# 1_power.net
KiCad netlist of a schematic drawn in Altium Designer
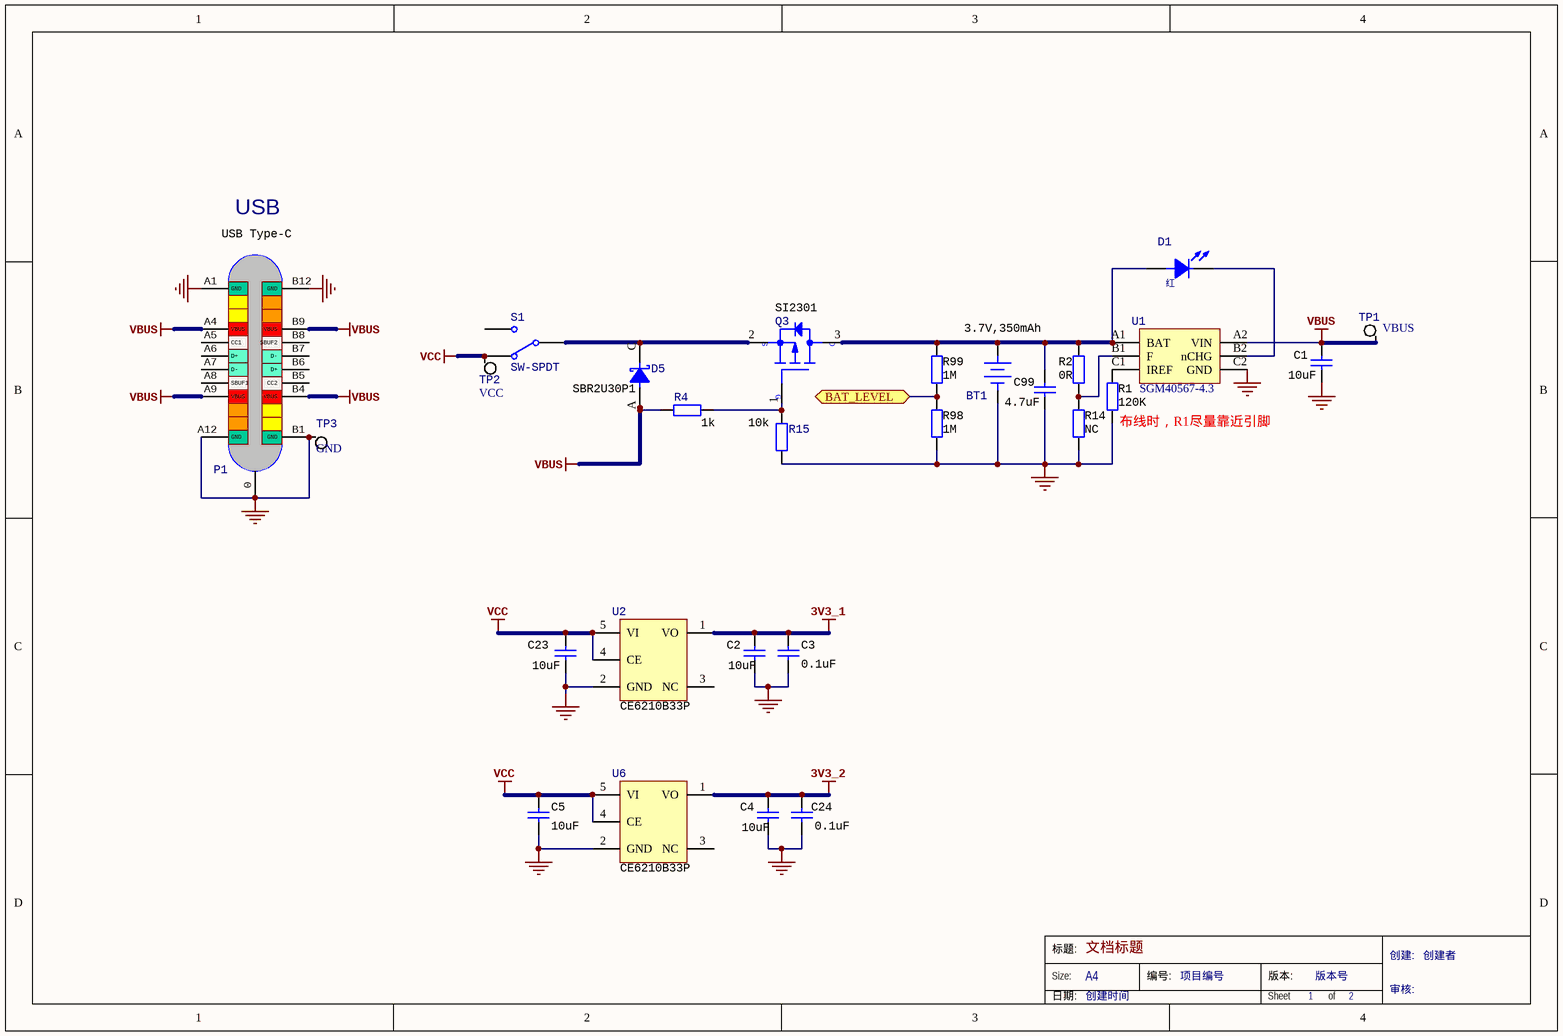
[diagram p0: 1.power.SchDoc]

(export (version "E")
  (design (tool "Eeschema 10.0.6"))
  (components
    (comp (ref "BT1")
      (value "3.7V,350mAh")
      (footprint "2P/1.0MM立式贴片座子")
      (description "4.2V Li-lon")
      (fields (field (name "MANUFACTURER") "?"))
      (libsource (lib "03.常用器件") (part "Battery"))
    )
    (comp (ref "C1")
      (value "10uF")
      (footprint "0603")
      (description "CAP, CERM, 0.01uF, 100V, +/-5%, X7R, 0603")
      (fields (field (name "PARTNUMBER") "06031C103JAT2A") (field (name "MANUFACTURER") "AVX"))
      (libsource (lib "03.常用器件") (part "CAP1_npol"))
    )
    (comp (ref "C2")
      (value "10uF")
      (footprint "0603")
      (description "CAP, CERM, 0.01uF, 100V, +/-5%, X7R, 0603")
      (fields (field (name "PARTNUMBER") "06031C103JAT2A") (field (name "MANUFACTURER") "AVX"))
      (libsource (lib "03.常用器件") (part "CAP1_npol"))
    )
    (comp (ref "C3")
      (value "0.1uF")
      (footprint "0402")
      (description "CAP, CERM, 0.01uF, 100V, +/-5%, X7R, 0603")
      (fields (field (name "PARTNUMBER") "06031C103JAT2A") (field (name "MANUFACTURER") "AVX"))
      (libsource (lib "03.常用器件") (part "CAP1_npol"))
    )
    (comp (ref "C4")
      (value "10uF")
      (footprint "0603")
      (description "CAP, CERM, 0.01uF, 100V, +/-5%, X7R, 0603")
      (fields (field (name "PARTNUMBER") "06031C103JAT2A") (field (name "MANUFACTURER") "AVX"))
      (libsource (lib "03.常用器件") (part "CAP1_npol"))
    )
    (comp (ref "C5")
      (value "10uF")
      (footprint "0603")
      (description "CAP, CERM, 0.01uF, 100V, +/-5%, X7R, 0603")
      (fields (field (name "PARTNUMBER") "06031C103JAT2A") (field (name "MANUFACTURER") "AVX"))
      (libsource (lib "03.常用器件") (part "CAP1_npol"))
    )
    (comp (ref "C23")
      (value "10uF")
      (footprint "0603")
      (description "CAP, CERM, 0.01uF, 100V, +/-5%, X7R, 0603")
      (fields (field (name "PARTNUMBER") "06031C103JAT2A") (field (name "MANUFACTURER") "AVX"))
      (libsource (lib "03.常用器件") (part "CAP1_npol"))
    )
    (comp (ref "C24")
      (value "0.1uF")
      (footprint "0402")
      (description "CAP, CERM, 0.01uF, 100V, +/-5%, X7R, 0603")
      (fields (field (name "PARTNUMBER") "06031C103JAT2A") (field (name "MANUFACTURER") "AVX"))
      (libsource (lib "03.常用器件") (part "CAP1_npol"))
    )
    (comp (ref "C99")
      (value "4.7uF")
      (footprint "0603")
      (description "CAP, CERM, 0.01uF, 100V, +/-5%, X7R, 0603")
      (fields (field (name "PARTNUMBER") "06031C103JAT2A") (field (name "MANUFACTURER") "AVX"))
      (libsource (lib "03.常用器件") (part "CAP1_npol"))
    )
    (comp (ref "D1")
      (value "红")
      (footprint "0603LED")
      (fields (field (name "MANUFACTURER") "?"))
      (libsource (lib "03.常用器件") (part "LED1"))
    )
    (comp (ref "D5")
      (value "SBR2U30P1")
      (footprint "POWERDI123")
      (fields (field (name "PARTNUMBER") "?") (field (name "PUBLISHER") "Altium Limited"))
      (libsource (lib "03.常用器件") (part "Diode_Schottky"))
    )
    (comp (ref "P1")
      (value "USB Type-C")
      (footprint "TYPC-16PIN")
      (libsource (lib "USB Type-C") (part "USB Type-C"))
    )
    (comp (ref "Q3")
      (value "SI2301")
      (footprint "SOT23-3")
      (fields (field (name "MANUFACTURER") "?"))
      (libsource (lib "03.常用器件") (part "PMOS"))
    )
    (comp (ref "R1")
      (value "120K")
      (footprint "0402")
      (description "RES, 1.0k ohm, 5%, 0.1W, 0603")
      (fields
        (field (name "PARTNUMBER") "RC0603JR-071KL")
        (field (name "MANUFACTURER") "Yageo America")
        (field (name "PUBLISHER") "Texas Instruments")
      )
      (libsource (lib "03.常用器件") (part "RES1"))
    )
    (comp (ref "R2")
      (value "0R")
      (footprint "0402")
      (description "RES, 1.0k ohm, 5%, 0.1W, 0603")
      (fields
        (field (name "PARTNUMBER") "RC0603JR-071KL")
        (field (name "MANUFACTURER") "Yageo America")
        (field (name "PUBLISHER") "Texas Instruments")
      )
      (libsource (lib "") (part "RES1_1"))
    )
    (comp (ref "R4")
      (value "1k")
      (footprint "R0402")
      (description "Resistor")
      (fields (field (name "PUBLISHER") "Altium Limited"))
      (libsource (lib "Miscellaneous Devices") (part "Res2"))
    )
    (comp (ref "R14")
      (value "NC")
      (footprint "0402")
      (description "RES, 1.0k ohm, 5%, 0.1W, 0603")
      (fields
        (field (name "PARTNUMBER") "RC0603JR-071KL")
        (field (name "MANUFACTURER") "Yageo America")
        (field (name "PUBLISHER") "Texas Instruments")
      )
      (libsource (lib "") (part "RES1_1"))
    )
    (comp (ref "R15")
      (value "10k")
      (footprint "R0402")
      (description "Resistor")
      (fields (field (name "PUBLISHER") "Altium Limited"))
      (libsource (lib "") (part "Res2_1"))
    )
    (comp (ref "R98")
      (value "1M")
      (footprint "0402")
      (description "RES, 1.0k ohm, 5%, 0.1W, 0603")
      (fields
        (field (name "PARTNUMBER") "RC0603JR-071KL")
        (field (name "MANUFACTURER") "Yageo America")
        (field (name "PUBLISHER") "Texas Instruments")
      )
      (libsource (lib "03.常用器件") (part "RES1"))
    )
    (comp (ref "R99")
      (value "1M")
      (footprint "0402")
      (description "RES, 1.0k ohm, 5%, 0.1W, 0603")
      (fields
        (field (name "PARTNUMBER") "RC0603JR-071KL")
        (field (name "MANUFACTURER") "Yageo America")
        (field (name "PUBLISHER") "Texas Instruments")
      )
      (libsource (lib "03.常用器件") (part "RES1"))
    )
    (comp (ref "S1")
      (value "SW-SPDT")
      (footprint "SW2")
      (description "SPDT Subminiature Toggle Switch, Right Angle Mounting, Vertical Actuation")
      (fields (field (name "PUBLISHER") "Altium Limited"))
      (libsource (lib "Miscellaneous Devices") (part "SW-SPDT"))
    )
    (comp (ref "TP1")
      (value "VBUS")
      (footprint "测试点")
      (description "Test Point")
      (libsource (lib "my_Schlib") (part "TP"))
    )
    (comp (ref "TP2")
      (value "VCC")
      (footprint "测试点")
      (description "Test Point")
      (libsource (lib "my_Schlib") (part "TP"))
    )
    (comp (ref "TP3")
      (value "GND")
      (footprint "测试点")
      (description "Test Point")
      (libsource (lib "my_Schlib") (part "TP"))
    )
    (comp (ref "U1")
      (value "SGM40567-4.3")
      (footprint "WLCSP-0.92×1.16-6B")
      (description "充电IC")
      (libsource (lib "SGM40567") (part "SGM40567"))
    )
    (comp (ref "U2")
      (value "CE6210B33P")
      (footprint "SOT89-5")
      (libsource (lib "altium-import") (part "root_0_AP2112K_"))
    )
    (comp (ref "U6")
      (value "CE6210B33P")
      (footprint "SOT89-5")
      (libsource (lib "altium-import") (part "root_0_AP2112K_"))
    )
  )
  (nets
    (net (code "1") (name "/BAT_LEVEL") (class "Default")
      (node (ref "R98") (pin "2") (pinfunction "2_2") (pintype "passive"))
      (node (ref "R99") (pin "1") (pinfunction "1_1") (pintype "passive"))
    )
    (net (code "2") (name "3V3_1") (class "Default")
      (node (ref "C2") (pin "1") (pinfunction "1_1") (pintype "passive"))
      (node (ref "C3") (pin "2") (pinfunction "2_2") (pintype "passive"))
      (node (ref "U2") (pin "1") (pinfunction "VO_1") (pintype "passive"))
    )
    (net (code "3") (name "3V3_2") (class "Default")
      (node (ref "C24") (pin "2") (pinfunction "2_2") (pintype "passive"))
      (node (ref "C4") (pin "1") (pinfunction "1_1") (pintype "passive"))
      (node (ref "U6") (pin "1") (pinfunction "VO_1") (pintype "passive"))
    )
    (net (code "4") (name "<NO NET>") (class "Default")
      (node (ref "BT1") (pin "2") (pinfunction "-_2") (pintype "passive"))
      (node (ref "C1") (pin "2") (pinfunction "2_2") (pintype "passive"))
      (node (ref "C2") (pin "2") (pinfunction "2_2") (pintype "passive"))
      (node (ref "C23") (pin "2") (pinfunction "2_2") (pintype "passive"))
      (node (ref "C24") (pin "1") (pinfunction "1_1") (pintype "passive"))
      (node (ref "C3") (pin "1") (pinfunction "1_1") (pintype "passive"))
      (node (ref "C4") (pin "2") (pinfunction "2_2") (pintype "passive"))
      (node (ref "C5") (pin "2") (pinfunction "2_2") (pintype "passive"))
      (node (ref "C99") (pin "2") (pinfunction "2_2") (pintype "passive"))
      (node (ref "P1") (pin "0") (pinfunction "Shield_0") (pintype "passive"))
      (node (ref "P1") (pin "A1") (pinfunction "GND_A1") (pintype "passive"))
      (node (ref "P1") (pin "A12") (pinfunction "GND_A12") (pintype "passive"))
      (node (ref "P1") (pin "B1") (pinfunction "GND_B1") (pintype "passive"))
      (node (ref "P1") (pin "B12") (pinfunction "GND_B12") (pintype "passive"))
      (node (ref "R1") (pin "1") (pinfunction "1_1") (pintype "passive"))
      (node (ref "R14") (pin "2") (pinfunction "2_2") (pintype "passive"))
      (node (ref "R15") (pin "1") (pinfunction "1_1") (pintype "passive"))
      (node (ref "R98") (pin "1") (pinfunction "1_1") (pintype "passive"))
      (node (ref "TP3") (pin "1") (pinfunction "1_1") (pintype "passive"))
      (node (ref "U1") (pin "C2") (pinfunction "GND_C2") (pintype "passive"))
      (node (ref "U2") (pin "2") (pinfunction "GND_2") (pintype "passive"))
      (node (ref "U6") (pin "2") (pinfunction "GND_2") (pintype "passive"))
    )
    (net (code "5") (name "Net-(BT1-+)") (class "Default")
      (node (ref "BT1") (pin "1") (pinfunction "+_1") (pintype "passive"))
      (node (ref "C99") (pin "1") (pinfunction "1_1") (pintype "passive"))
      (node (ref "D1") (pin "A") (pinfunction "ANODE_A") (pintype "passive"))
      (node (ref "Q3") (pin "3") (pinfunction "DRAIN_3") (pintype "passive"))
      (node (ref "R2") (pin "1") (pinfunction "1_1") (pintype "passive"))
      (node (ref "R99") (pin "2") (pinfunction "2_2") (pintype "passive"))
      (node (ref "U1") (pin "A1") (pinfunction "BAT_A1") (pintype "passive"))
    )
    (net (code "6") (name "Net-(D1-CATHODE)") (class "Default")
      (node (ref "D1") (pin "C") (pinfunction "CATHODE_C") (pintype "passive"))
      (node (ref "U1") (pin "B2") (pinfunction "nCHG_B2") (pintype "passive"))
    )
    (net (code "7") (name "Net-(D5-CATHODE)") (class "Default")
      (node (ref "D5") (pin "C") (pinfunction "CATHODE_C") (pintype "passive"))
      (node (ref "Q3") (pin "2") (pinfunction "SOURCE_2") (pintype "passive"))
      (node (ref "S1") (pin "2") (pinfunction "2_2") (pintype "passive"))
    )
    (net (code "8") (name "Net-(Q3-GATE)") (class "Default")
      (node (ref "Q3") (pin "1") (pinfunction "GATE_1") (pintype "passive"))
      (node (ref "R15") (pin "2") (pinfunction "2_2") (pintype "passive"))
      (node (ref "R4") (pin "1") (pinfunction "1_1") (pintype "passive"))
    )
    (net (code "9") (name "Net-(U1-F)") (class "Default")
      (node (ref "R14") (pin "1") (pinfunction "1_1") (pintype "passive"))
      (node (ref "R2") (pin "2") (pinfunction "2_2") (pintype "passive"))
      (node (ref "U1") (pin "B1") (pinfunction "F_B1") (pintype "passive"))
    )
    (net (code "10") (name "Net-(U1-IREF)") (class "Default")
      (node (ref "R1") (pin "2") (pinfunction "2_2") (pintype "passive"))
      (node (ref "U1") (pin "C1") (pinfunction "IREF_C1") (pintype "passive"))
    )
    (net (code "11") (name "VBUS") (class "Default")
      (node (ref "C1") (pin "1") (pinfunction "1_1") (pintype "passive"))
      (node (ref "D5") (pin "A") (pinfunction "ANODE_A") (pintype "passive"))
      (node (ref "P1") (pin "A4") (pinfunction "VBUS_A4") (pintype "passive"))
      (node (ref "P1") (pin "A9") (pinfunction "VBUS_A9") (pintype "passive"))
      (node (ref "P1") (pin "B4") (pinfunction "VBUS_B4") (pintype "passive"))
      (node (ref "P1") (pin "B9") (pinfunction "VBUS_B9") (pintype "passive"))
      (node (ref "R4") (pin "2") (pinfunction "2_2") (pintype "passive"))
      (node (ref "TP1") (pin "1") (pinfunction "1_1") (pintype "passive"))
      (node (ref "U1") (pin "A2") (pinfunction "VIN_A2") (pintype "passive"))
    )
    (net (code "12") (name "VCC") (class "Default")
      (node (ref "C23") (pin "1") (pinfunction "1_1") (pintype "passive"))
      (node (ref "C5") (pin "1") (pinfunction "1_1") (pintype "passive"))
      (node (ref "S1") (pin "3") (pinfunction "3_3") (pintype "passive"))
      (node (ref "TP2") (pin "1") (pinfunction "1_1") (pintype "passive"))
      (node (ref "U2") (pin "4") (pinfunction "CE_4") (pintype "passive"))
      (node (ref "U2") (pin "5") (pinfunction "VI_5") (pintype "passive"))
      (node (ref "U6") (pin "4") (pinfunction "CE_4") (pintype "passive"))
      (node (ref "U6") (pin "5") (pinfunction "VI_5") (pintype "passive"))
    )
    (net (code "13") (name "unconnected-(P1-CC1-PadA5)") (class "Default")
      (node (ref "P1") (pin "A5") (pinfunction "CC1_A5") (pintype "passive"))
    )
    (net (code "14") (name "unconnected-(P1-CC2-PadB5)") (class "Default")
      (node (ref "P1") (pin "B5") (pinfunction "CC2_B5") (pintype "passive"))
    )
    (net (code "15") (name "unconnected-(P1-D+-PadA6)") (class "Default")
      (node (ref "P1") (pin "A6") (pinfunction "D+_A6") (pintype "passive"))
    )
    (net (code "16") (name "unconnected-(P1-D+-PadB6)") (class "Default")
      (node (ref "P1") (pin "B6") (pinfunction "D+_B6") (pintype "passive"))
    )
    (net (code "17") (name "unconnected-(P1-D--PadA7)") (class "Default")
      (node (ref "P1") (pin "A7") (pinfunction "D-_A7") (pintype "passive"))
    )
    (net (code "18") (name "unconnected-(P1-D--PadB7)") (class "Default")
      (node (ref "P1") (pin "B7") (pinfunction "D-_B7") (pintype "passive"))
    )
    (net (code "19") (name "unconnected-(P1-SBUF1-PadA8)") (class "Default")
      (node (ref "P1") (pin "A8") (pinfunction "SBUF1_A8") (pintype "passive"))
    )
    (net (code "20") (name "unconnected-(P1-SBUF2-PadB8)") (class "Default")
      (node (ref "P1") (pin "B8") (pinfunction "SBUF2_B8") (pintype "passive"))
    )
    (net (code "21") (name "unconnected-(S1-Pad1)") (class "Default")
      (node (ref "S1") (pin "1") (pinfunction "1_1") (pintype "passive"))
    )
    (net (code "22") (name "unconnected-(U2-NC-Pad3)") (class "Default")
      (node (ref "U2") (pin "3") (pinfunction "NC_3") (pintype "passive"))
    )
    (net (code "23") (name "unconnected-(U6-NC-Pad3)") (class "Default")
      (node (ref "U6") (pin "3") (pinfunction "NC_3") (pintype "passive"))
    )
  )
)
